# 5VACDC.net
KiCad netlist of a schematic drawn in EAGLE
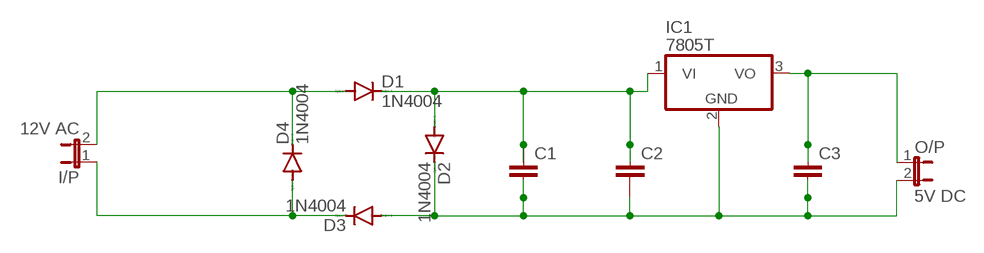
[diagram p0: schematic, sheet 1]

(export (version "E")
  (design (tool "Eeschema 10.0.6"))
  (components
    (comp (ref "C1")
      (value "C2,5-3")
      (footprint "eagle-import:C2.5-3")
      (libsource (lib "eagle-import") (part "C2,5-3"))
    )
    (comp (ref "C2")
      (value "C2,5-3")
      (footprint "eagle-import:C2.5-3")
      (libsource (lib "eagle-import") (part "C2,5-3"))
    )
    (comp (ref "C3")
      (value "C2,5-3")
      (footprint "eagle-import:C2.5-3")
      (libsource (lib "eagle-import") (part "C2,5-3"))
    )
    (comp (ref "D1")
      (value "1N4004")
      (footprint "eagle-import:DO41-10")
      (libsource (lib "eagle-import") (part "1N4004"))
    )
    (comp (ref "D2")
      (value "1N4004")
      (footprint "eagle-import:DO41-10")
      (libsource (lib "eagle-import") (part "1N4004"))
    )
    (comp (ref "D3")
      (value "1N4004")
      (footprint "eagle-import:DO41-10")
      (libsource (lib "eagle-import") (part "1N4004"))
    )
    (comp (ref "D4")
      (value "1N4004")
      (footprint "eagle-import:DO41-10")
      (libsource (lib "eagle-import") (part "1N4004"))
    )
    (comp (ref "I/P")
      (value "12V AC")
      (footprint "eagle-import:JP1")
      (libsource (lib "eagle-import") (part "JP1E"))
    )
    (comp (ref "IC1")
      (value "7805T")
      (footprint "eagle-import:TO220H")
      (libsource (lib "eagle-import") (part "78T05"))
    )
    (comp (ref "O/P")
      (value "5V DC")
      (footprint "eagle-import:JP1")
      (libsource (lib "eagle-import") (part "JP1E"))
    )
  )
  (nets
    (net (code "1") (name "Net-(D1-PadA)") (class "Default")
      (node (ref "D1") (pin "A") (pinfunction "A_A") (pintype "passive"))
      (node (ref "D4") (pin "C") (pinfunction "C_C") (pintype "passive"))
      (node (ref "I/P") (pin "2") (pinfunction "2_2") (pintype "passive"))
    )
    (net (code "2") (name "Net-(D3-PadC)") (class "Default")
      (node (ref "D3") (pin "C") (pinfunction "C_C") (pintype "passive"))
      (node (ref "D4") (pin "A") (pinfunction "A_A") (pintype "passive"))
      (node (ref "I/P") (pin "1") (pinfunction "1_1") (pintype "passive"))
    )
    (net (code "3") (name "Net-(IC1-GND)") (class "Default")
      (node (ref "C1") (pin "2") (pinfunction "2_2") (pintype "passive"))
      (node (ref "C2") (pin "2") (pinfunction "2_2") (pintype "passive"))
      (node (ref "C3") (pin "2") (pinfunction "2_2") (pintype "passive"))
      (node (ref "D2") (pin "C") (pinfunction "C_C") (pintype "passive"))
      (node (ref "D3") (pin "A") (pinfunction "A_A") (pintype "passive"))
      (node (ref "IC1") (pin "2") (pinfunction "GND_2") (pintype "passive"))
      (node (ref "O/P") (pin "2") (pinfunction "2_2") (pintype "passive"))
    )
    (net (code "4") (name "Net-(IC1-VI)") (class "Default")
      (node (ref "C1") (pin "1") (pinfunction "1_1") (pintype "passive"))
      (node (ref "C2") (pin "1") (pinfunction "1_1") (pintype "passive"))
      (node (ref "D1") (pin "C") (pinfunction "C_C") (pintype "passive"))
      (node (ref "D2") (pin "A") (pinfunction "A_A") (pintype "passive"))
      (node (ref "IC1") (pin "1") (pinfunction "VI_1") (pintype "input"))
    )
    (net (code "5") (name "Net-(IC1-VO)") (class "Default")
      (node (ref "C3") (pin "1") (pinfunction "1_1") (pintype "passive"))
      (node (ref "IC1") (pin "3") (pinfunction "VO_3") (pintype "passive"))
      (node (ref "O/P") (pin "1") (pinfunction "1_1") (pintype "passive"))
    )
  )
)
